# PPS_schematic.net
KiCad netlist of a schematic drawn in EAGLE
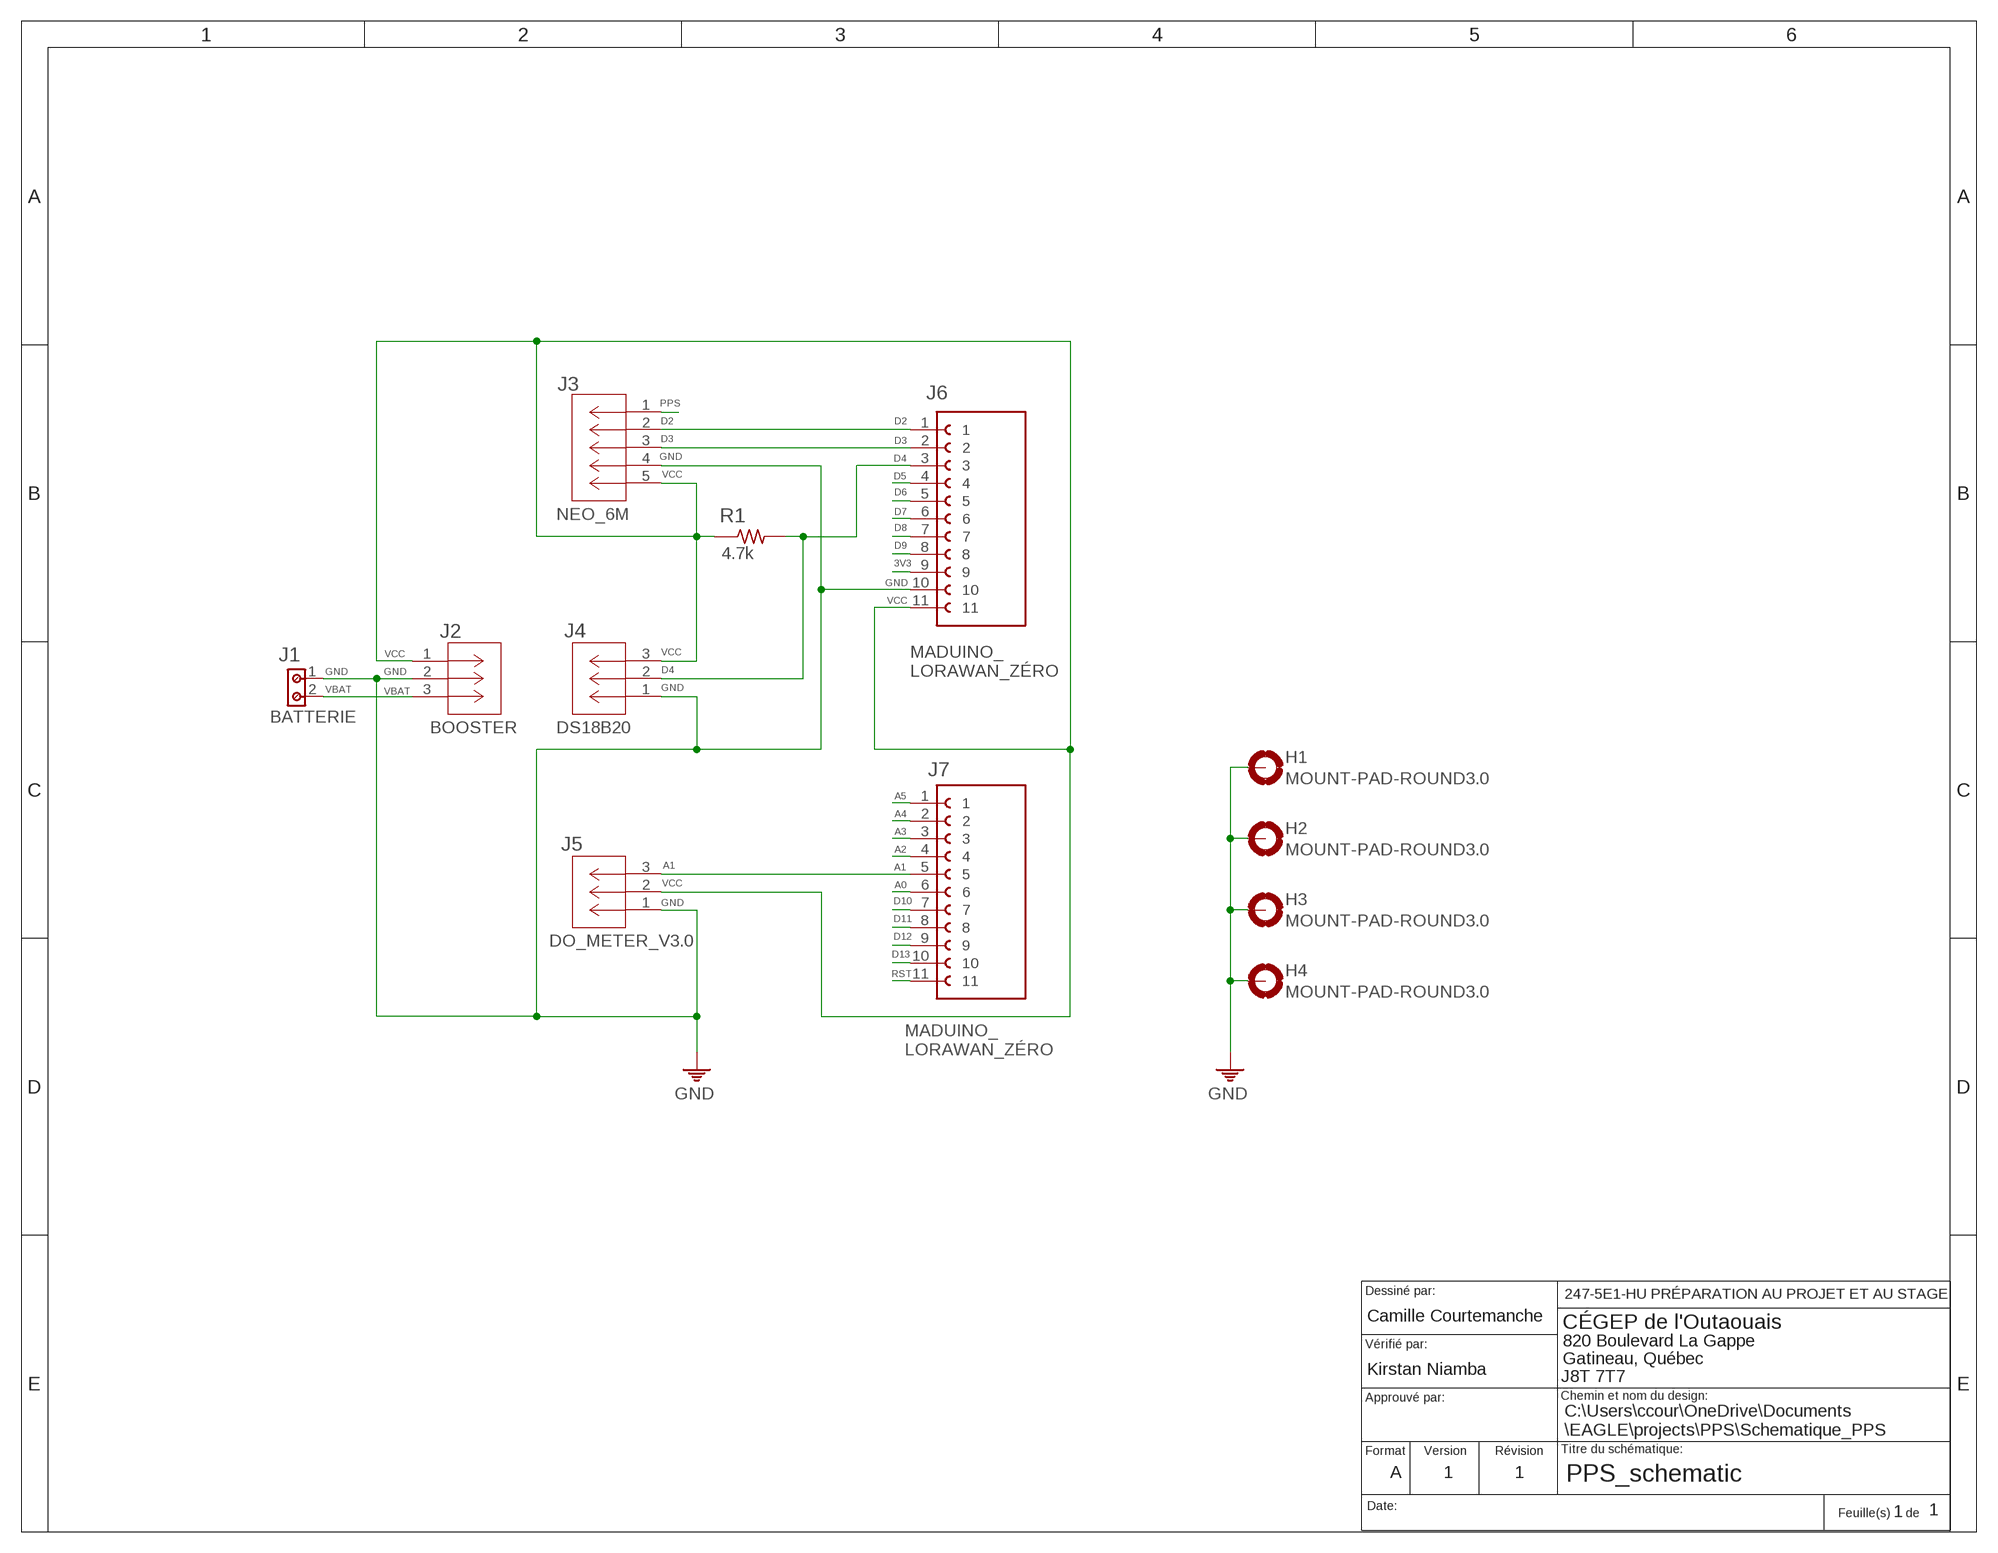
[diagram p0: schematic, sheet 1]

(export (version "E")
  (design (tool "Eeschema 10.0.6"))
  (components
    (comp (ref "H1")
      (value "MOUNT-PAD-ROUND3.0")
      (footprint "eagle-import:3,0-PAD")
      (libsource (lib "eagle-import") (part "MOUNT-PAD-ROUND3.0"))
    )
    (comp (ref "H2")
      (value "MOUNT-PAD-ROUND3.0")
      (footprint "eagle-import:3,0-PAD")
      (libsource (lib "eagle-import") (part "MOUNT-PAD-ROUND3.0"))
    )
    (comp (ref "H3")
      (value "MOUNT-PAD-ROUND3.0")
      (footprint "eagle-import:3,0-PAD")
      (libsource (lib "eagle-import") (part "MOUNT-PAD-ROUND3.0"))
    )
    (comp (ref "H4")
      (value "MOUNT-PAD-ROUND3.0")
      (footprint "eagle-import:3,0-PAD")
      (libsource (lib "eagle-import") (part "MOUNT-PAD-ROUND3.0"))
    )
    (comp (ref "J1")
      (value "Batterie")
      (footprint "eagle-import:691137710002")
      (libsource (lib "eagle-import") (part "691137710002"))
    )
    (comp (ref "J2")
      (value "BOOSTER")
      (footprint "eagle-import:CON3_1X3_TU_HTS_SAI")
      (fields
        (field (name "MANUFACTURER_PART_NUMBER") "TS-103-T-A")
        (field (name "COPYRIGHT") "Copyright (C) 2024 Ultra Librarian. All rights reserved.")
      )
      (libsource (lib "eagle-import") (part "TS-103-T-ACON3_1X3_TU_HTS_SAI"))
    )
    (comp (ref "J3")
      (value "NEO-6M")
      (footprint "eagle-import:CONN5_1LFBN-RC_SUL")
      (fields
        (field (name "MANUFACTURER_PART_NUMBER") "PPTC051LFBN-RC")
        (field (name "COPYRIGHT") "Copyright (C) 2024 Ultra Librarian. All rights reserved.")
      )
      (libsource (lib "eagle-import") (part "PPTC051LFBN-RCCONN5_1LFBN-RC_SUL"))
    )
    (comp (ref "J4")
      (value "DS18B20")
      (footprint "eagle-import:CONN_PPTC031_SUL")
      (fields
        (field (name "MANUFACTURER_PART_NUMBER") "PPTC031LFBN-RC")
        (field (name "COPYRIGHT") "Copyright (C) 2024 Ultra Librarian. All rights reserved.")
      )
      (libsource (lib "eagle-import") (part "PPTC031LFBN-RCCONN_PPTC031_SUL"))
    )
    (comp (ref "J5")
      (value "D0_METTER_v3.0")
      (footprint "eagle-import:CONN_PPTC031_SUL")
      (fields
        (field (name "MANUFACTURER_PART_NUMBER") "PPTC031LFBN-RC")
        (field (name "COPYRIGHT") "Copyright (C) 2024 Ultra Librarian. All rights reserved.")
      )
      (libsource (lib "eagle-import") (part "PPTC031LFBN-RCCONN_PPTC031_SUL"))
    )
    (comp (ref "J6")
      (value "MADUINO_LORAWAN_ZÉRO")
      (footprint "eagle-import:HARWIN_M20-7821146")
      (fields (field (name "MANUFACTURER") "HARWIN"))
      (libsource (lib "eagle-import") (part "M20-7821146"))
    )
    (comp (ref "J7")
      (value "MADUINO_LORAWAN_ZÉRO")
      (footprint "eagle-import:HARWIN_M20-7821146")
      (fields (field (name "MANUFACTURER") "HARWIN"))
      (libsource (lib "eagle-import") (part "M20-7821146"))
    )
    (comp (ref "R1")
      (value "4.7k")
      (footprint "eagle-import:M1206")
      (libsource (lib "eagle-import") (part "RM1206"))
    )
  )
  (nets
    (net (code "1") (name "/3V3") (class "Default")
      (node (ref "J6") (pin "9") (pinfunction "9_9") (pintype "passive"))
    )
    (net (code "2") (name "/A0") (class "Default")
      (node (ref "J7") (pin "6") (pinfunction "6_6") (pintype "passive"))
    )
    (net (code "3") (name "/A1") (class "Default")
      (node (ref "J5") (pin "3") (pinfunction "3_3") (pintype "passive"))
      (node (ref "J7") (pin "5") (pinfunction "5_5") (pintype "passive"))
    )
    (net (code "4") (name "/A2") (class "Default")
      (node (ref "J7") (pin "4") (pinfunction "4_4") (pintype "passive"))
    )
    (net (code "5") (name "/A3") (class "Default")
      (node (ref "J7") (pin "3") (pinfunction "3_3") (pintype "passive"))
    )
    (net (code "6") (name "/A4") (class "Default")
      (node (ref "J7") (pin "2") (pinfunction "2_2") (pintype "passive"))
    )
    (net (code "7") (name "/A5") (class "Default")
      (node (ref "J7") (pin "1") (pinfunction "1_1") (pintype "passive"))
    )
    (net (code "8") (name "/D2") (class "Default")
      (node (ref "J3") (pin "2") (pinfunction "2_2") (pintype "passive"))
      (node (ref "J6") (pin "1") (pinfunction "1_1") (pintype "passive"))
    )
    (net (code "9") (name "/D3") (class "Default")
      (node (ref "J3") (pin "3") (pinfunction "3_3") (pintype "passive"))
      (node (ref "J6") (pin "2") (pinfunction "2_2") (pintype "passive"))
    )
    (net (code "10") (name "/D4") (class "Default")
      (node (ref "J4") (pin "2") (pinfunction "2_2") (pintype "passive"))
      (node (ref "J6") (pin "3") (pinfunction "3_3") (pintype "passive"))
      (node (ref "R1") (pin "2") (pinfunction "2_2") (pintype "passive"))
    )
    (net (code "11") (name "/D5") (class "Default")
      (node (ref "J6") (pin "4") (pinfunction "4_4") (pintype "passive"))
    )
    (net (code "12") (name "/D6") (class "Default")
      (node (ref "J6") (pin "5") (pinfunction "5_5") (pintype "passive"))
    )
    (net (code "13") (name "/D7") (class "Default")
      (node (ref "J6") (pin "6") (pinfunction "6_6") (pintype "passive"))
    )
    (net (code "14") (name "/D8") (class "Default")
      (node (ref "J6") (pin "7") (pinfunction "7_7") (pintype "passive"))
    )
    (net (code "15") (name "/D9") (class "Default")
      (node (ref "J6") (pin "8") (pinfunction "8_8") (pintype "passive"))
    )
    (net (code "16") (name "/D10") (class "Default")
      (node (ref "J7") (pin "7") (pinfunction "7_7") (pintype "passive"))
    )
    (net (code "17") (name "/D11") (class "Default")
      (node (ref "J7") (pin "8") (pinfunction "8_8") (pintype "passive"))
    )
    (net (code "18") (name "/D12") (class "Default")
      (node (ref "J7") (pin "9") (pinfunction "9_9") (pintype "passive"))
    )
    (net (code "19") (name "/D13") (class "Default")
      (node (ref "J7") (pin "10") (pinfunction "10_10") (pintype "passive"))
    )
    (net (code "20") (name "/PPS") (class "Default")
      (node (ref "J3") (pin "1") (pinfunction "1_1") (pintype "passive"))
    )
    (net (code "21") (name "/RST") (class "Default")
      (node (ref "J7") (pin "11") (pinfunction "11_11") (pintype "passive"))
    )
    (net (code "22") (name "/VBAT") (class "Default")
      (node (ref "J1") (pin "2") (pinfunction "2_2") (pintype "passive"))
      (node (ref "J2") (pin "3") (pinfunction "3_3") (pintype "passive"))
    )
    (net (code "23") (name "/VCC") (class "Default")
      (node (ref "J2") (pin "1") (pinfunction "1_1") (pintype "passive"))
      (node (ref "J3") (pin "5") (pinfunction "5_5") (pintype "passive"))
      (node (ref "J4") (pin "3") (pinfunction "3_3") (pintype "passive"))
      (node (ref "J5") (pin "2") (pinfunction "2_2") (pintype "passive"))
      (node (ref "J6") (pin "11") (pinfunction "11_11") (pintype "passive"))
      (node (ref "R1") (pin "1") (pinfunction "1_1") (pintype "passive"))
    )
    (net (code "24") (name "GND") (class "Default")
      (node (ref "H1") (pin "B3,0") (pinfunction "MOUNT_B3,0") (pintype "passive"))
      (node (ref "H2") (pin "B3,0") (pinfunction "MOUNT_B3,0") (pintype "passive"))
      (node (ref "H3") (pin "B3,0") (pinfunction "MOUNT_B3,0") (pintype "passive"))
      (node (ref "H4") (pin "B3,0") (pinfunction "MOUNT_B3,0") (pintype "passive"))
      (node (ref "J1") (pin "1") (pinfunction "1_1") (pintype "passive"))
      (node (ref "J2") (pin "2") (pinfunction "2_2") (pintype "passive"))
      (node (ref "J3") (pin "4") (pinfunction "4_4") (pintype "passive"))
      (node (ref "J4") (pin "1") (pinfunction "1_1") (pintype "passive"))
      (node (ref "J5") (pin "1") (pinfunction "1_1") (pintype "passive"))
      (node (ref "J6") (pin "10") (pinfunction "10_10") (pintype "passive"))
    )
  )
)
